# mux.net
KiCad netlist of a schematic drawn in Altium Designer
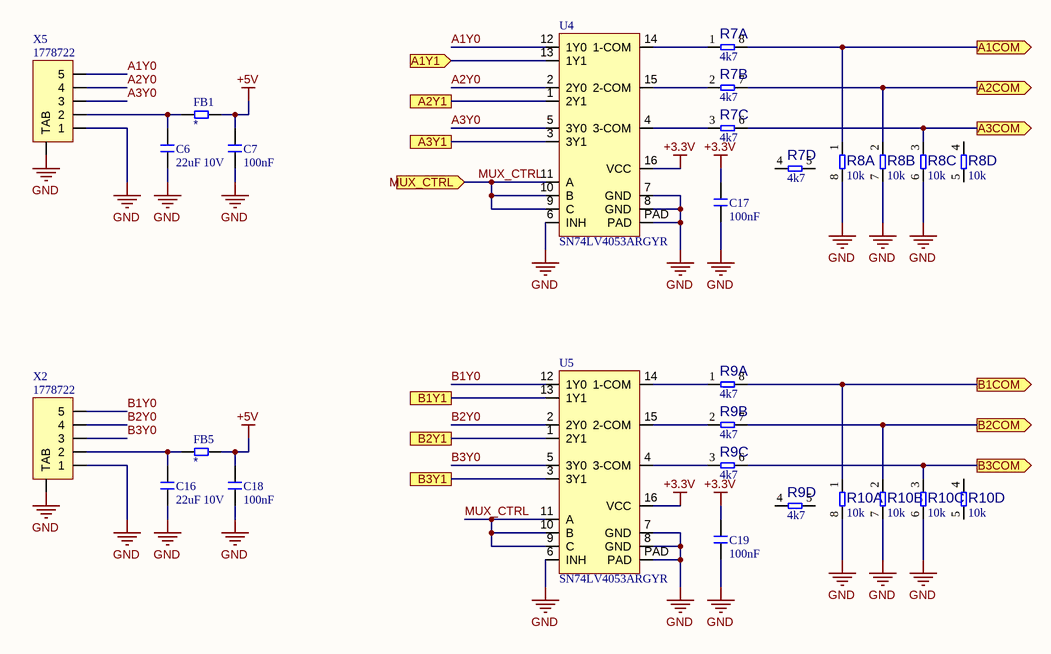
[diagram p0: mux.SchDoc]

(export (version "E")
  (design (tool "Eeschema 10.0.6"))
  (components
    (comp (ref "C6")
      (value "22uF 10V")
      (footprint "C1210_N")
      (description "Capacitor MLCC")
      (fields
        (field (name "MANUFACTURER") "Yageo")
        (field (name "MANUFACTURER PART NUMBER") "CC0603KRX7R9BB104")
      )
      (libsource (lib "wes") (part "Capacitor"))
    )
    (comp (ref "C7")
      (value "100nF")
      (footprint "C0603_N")
      (description "Capacitor MLCC")
      (fields
        (field (name "MANUFACTURER") "Yageo")
        (field (name "MANUFACTURER PART NUMBER") "CC0603KRX7R9BB104")
      )
      (libsource (lib "wes") (part "Capacitor"))
    )
    (comp (ref "C16")
      (value "22uF 10V")
      (footprint "C1210_N")
      (description "Capacitor MLCC")
      (fields
        (field (name "MANUFACTURER") "Yageo")
        (field (name "MANUFACTURER PART NUMBER") "CC0603KRX7R9BB104")
      )
      (libsource (lib "wes") (part "Capacitor"))
    )
    (comp (ref "C17")
      (value "100nF")
      (footprint "C0603_N")
      (description "Capacitor MLCC")
      (fields
        (field (name "MANUFACTURER") "Yageo")
        (field (name "MANUFACTURER PART NUMBER") "CC0603KRX7R9BB104")
      )
      (libsource (lib "wes") (part "Capacitor"))
    )
    (comp (ref "C18")
      (value "100nF")
      (footprint "C0603_N")
      (description "Capacitor MLCC")
      (fields
        (field (name "MANUFACTURER") "Yageo")
        (field (name "MANUFACTURER PART NUMBER") "CC0603KRX7R9BB104")
      )
      (libsource (lib "wes") (part "Capacitor"))
    )
    (comp (ref "C19")
      (value "100nF")
      (footprint "C0603_N")
      (description "Capacitor MLCC")
      (fields
        (field (name "MANUFACTURER") "Yageo")
        (field (name "MANUFACTURER PART NUMBER") "CC0603KRX7R9BB104")
      )
      (libsource (lib "wes") (part "Capacitor"))
    )
    (comp (ref "FB1")
      (value "Ferrite")
      (footprint "R0603")
      (fields (field (name "ALTIUM_VALUE") "*") (field (name "PUBLISHER") "Altium Limited"))
      (libsource (lib "wes") (part "Resistor"))
    )
    (comp (ref "FB5")
      (value "Ferrite")
      (footprint "R0603")
      (fields (field (name "ALTIUM_VALUE") "*") (field (name "PUBLISHER") "Altium Limited"))
      (libsource (lib "wes") (part "Resistor"))
    )
    (comp (ref "R7") (value "4k7") (footprint "YC164") (libsource (lib "wes") (part "Resistor Array - 4P")))
    (comp (ref "R8") (value "10k") (footprint "YC164") (libsource (lib "wes") (part "Resistor Array - 4P")))
    (comp (ref "R9") (value "4k7") (footprint "YC164") (libsource (lib "wes") (part "Resistor Array - 4P")))
    (comp (ref "R10") (value "10k") (footprint "YC164") (libsource (lib "wes") (part "Resistor Array - 4P")))
    (comp (ref "U4")
      (value "SN74LV4053ARGYR")
      (footprint "QFN16")
      (libsource (lib "wes") (part "SN74LV4053ARGYR"))
    )
    (comp (ref "U5")
      (value "SN74LV4053ARGYR")
      (footprint "QFN16")
      (libsource (lib "wes") (part "SN74LV4053ARGYR"))
    )
    (comp (ref "X2")
      (value "1778722")
      (footprint "PTSM-5W-V-SMD")
      (libsource (lib "wes") (part "Connector 5W - TAB"))
    )
    (comp (ref "X5")
      (value "1778722")
      (footprint "PTSM-5W-V-SMD")
      (libsource (lib "wes") (part "Connector 5W - TAB"))
    )
  )
  (nets
    (net (code "1") (name "+3.3V") (class "Default")
      (node (ref "C17") (pin "1") (pintype "passive"))
      (node (ref "C19") (pin "1") (pintype "passive"))
      (node (ref "U4") (pin "16") (pinfunction "VCC_16") (pintype "passive"))
      (node (ref "U5") (pin "16") (pinfunction "VCC_16") (pintype "passive"))
    )
    (net (code "2") (name "+5V") (class "Default")
      (node (ref "C18") (pin "1") (pintype "passive"))
      (node (ref "C7") (pin "1") (pintype "passive"))
      (node (ref "FB1") (pin "2") (pinfunction "2_2") (pintype "passive"))
      (node (ref "FB5") (pin "2") (pinfunction "2_2") (pintype "passive"))
    )
    (net (code "3") (name "/A1COM") (class "Default")
      (node (ref "R7") (pin "8") (pinfunction "8_8") (pintype "passive"))
      (node (ref "R8") (pin "1") (pinfunction "1_1") (pintype "passive"))
    )
    (net (code "4") (name "/A1Y0") (class "Default")
      (node (ref "U4") (pin "12") (pinfunction "1Y0_12") (pintype "passive"))
      (node (ref "X5") (pin "5") (pinfunction "5_5") (pintype "power_in"))
    )
    (net (code "5") (name "/A1Y1") (class "Default")
      (node (ref "U4") (pin "13") (pinfunction "1Y1_13") (pintype "passive"))
    )
    (net (code "6") (name "/A2COM") (class "Default")
      (node (ref "R7") (pin "7") (pinfunction "7_7") (pintype "passive"))
      (node (ref "R8") (pin "2") (pinfunction "2_2") (pintype "passive"))
    )
    (net (code "7") (name "/A2Y0") (class "Default")
      (node (ref "U4") (pin "2") (pinfunction "2Y0_2") (pintype "passive"))
      (node (ref "X5") (pin "4") (pinfunction "4_4") (pintype "power_in"))
    )
    (net (code "8") (name "/A2Y1") (class "Default")
      (node (ref "U4") (pin "1") (pinfunction "2Y1_1") (pintype "passive"))
    )
    (net (code "9") (name "/A3COM") (class "Default")
      (node (ref "R7") (pin "6") (pinfunction "6_6") (pintype "passive"))
      (node (ref "R8") (pin "3") (pinfunction "3_3") (pintype "passive"))
    )
    (net (code "10") (name "/A3Y0") (class "Default")
      (node (ref "U4") (pin "5") (pinfunction "3Y0_5") (pintype "passive"))
      (node (ref "X5") (pin "3") (pinfunction "3_3") (pintype "power_in"))
    )
    (net (code "11") (name "/A3Y1") (class "Default")
      (node (ref "U4") (pin "3") (pinfunction "3Y1_3") (pintype "passive"))
    )
    (net (code "12") (name "/B1COM") (class "Default")
      (node (ref "R10") (pin "1") (pinfunction "1_1") (pintype "passive"))
      (node (ref "R9") (pin "8") (pinfunction "8_8") (pintype "passive"))
    )
    (net (code "13") (name "/B1Y0") (class "Default")
      (node (ref "U5") (pin "12") (pinfunction "1Y0_12") (pintype "passive"))
      (node (ref "X2") (pin "5") (pinfunction "5_5") (pintype "power_in"))
    )
    (net (code "14") (name "/B1Y1") (class "Default")
      (node (ref "U5") (pin "13") (pinfunction "1Y1_13") (pintype "passive"))
    )
    (net (code "15") (name "/B2COM") (class "Default")
      (node (ref "R10") (pin "2") (pinfunction "2_2") (pintype "passive"))
      (node (ref "R9") (pin "7") (pinfunction "7_7") (pintype "passive"))
    )
    (net (code "16") (name "/B2Y0") (class "Default")
      (node (ref "U5") (pin "2") (pinfunction "2Y0_2") (pintype "passive"))
      (node (ref "X2") (pin "4") (pinfunction "4_4") (pintype "power_in"))
    )
    (net (code "17") (name "/B2Y1") (class "Default")
      (node (ref "U5") (pin "1") (pinfunction "2Y1_1") (pintype "passive"))
    )
    (net (code "18") (name "/B3COM") (class "Default")
      (node (ref "R10") (pin "3") (pinfunction "3_3") (pintype "passive"))
      (node (ref "R9") (pin "6") (pinfunction "6_6") (pintype "passive"))
    )
    (net (code "19") (name "/B3Y0") (class "Default")
      (node (ref "U5") (pin "5") (pinfunction "3Y0_5") (pintype "passive"))
      (node (ref "X2") (pin "3") (pinfunction "3_3") (pintype "power_in"))
    )
    (net (code "20") (name "/B3Y1") (class "Default")
      (node (ref "U5") (pin "3") (pinfunction "3Y1_3") (pintype "passive"))
    )
    (net (code "21") (name "/MUX_CTRL") (class "Default")
      (node (ref "U4") (pin "10") (pinfunction "B_10") (pintype "passive"))
      (node (ref "U4") (pin "11") (pinfunction "A_11") (pintype "passive"))
      (node (ref "U4") (pin "9") (pinfunction "C_9") (pintype "passive"))
      (node (ref "U5") (pin "10") (pinfunction "B_10") (pintype "passive"))
      (node (ref "U5") (pin "11") (pinfunction "A_11") (pintype "passive"))
      (node (ref "U5") (pin "9") (pinfunction "C_9") (pintype "passive"))
    )
    (net (code "22") (name "GND") (class "Default")
      (node (ref "C16") (pin "2") (pintype "passive"))
      (node (ref "C17") (pin "2") (pintype "passive"))
      (node (ref "C18") (pin "2") (pintype "passive"))
      (node (ref "C19") (pin "2") (pintype "passive"))
      (node (ref "C6") (pin "2") (pintype "passive"))
      (node (ref "C7") (pin "2") (pintype "passive"))
      (node (ref "R10") (pin "6") (pinfunction "6_6") (pintype "passive"))
      (node (ref "R10") (pin "7") (pinfunction "7_7") (pintype "passive"))
      (node (ref "R10") (pin "8") (pinfunction "8_8") (pintype "passive"))
      (node (ref "R8") (pin "6") (pinfunction "6_6") (pintype "passive"))
      (node (ref "R8") (pin "7") (pinfunction "7_7") (pintype "passive"))
      (node (ref "R8") (pin "8") (pinfunction "8_8") (pintype "passive"))
      (node (ref "U4") (pin "6") (pinfunction "INH_6") (pintype "passive"))
      (node (ref "U4") (pin "7") (pinfunction "GND_7") (pintype "passive"))
      (node (ref "U4") (pin "8") (pinfunction "GND_8") (pintype "passive"))
      (node (ref "U4") (pin "PAD") (pinfunction "PAD_PAD") (pintype "passive"))
      (node (ref "U5") (pin "6") (pinfunction "INH_6") (pintype "passive"))
      (node (ref "U5") (pin "7") (pinfunction "GND_7") (pintype "passive"))
      (node (ref "U5") (pin "8") (pinfunction "GND_8") (pintype "passive"))
      (node (ref "U5") (pin "PAD") (pinfunction "PAD_PAD") (pintype "passive"))
      (node (ref "X2") (pin "1") (pinfunction "1_1") (pintype "power_in"))
      (node (ref "X2") (pin "TAB") (pinfunction "TAB_TAB") (pintype "power_in"))
      (node (ref "X5") (pin "1") (pinfunction "1_1") (pintype "power_in"))
      (node (ref "X5") (pin "TAB") (pinfunction "TAB_TAB") (pintype "power_in"))
    )
    (net (code "23") (name "Net-(C6-Pad1)") (class "Default")
      (node (ref "C6") (pin "1") (pintype "passive"))
      (node (ref "FB1") (pin "1") (pinfunction "1_1") (pintype "passive"))
      (node (ref "X5") (pin "2") (pinfunction "2_2") (pintype "power_in"))
    )
    (net (code "24") (name "Net-(C16-Pad1)") (class "Default")
      (node (ref "C16") (pin "1") (pintype "passive"))
      (node (ref "FB5") (pin "1") (pinfunction "1_1") (pintype "passive"))
      (node (ref "X2") (pin "2") (pinfunction "2_2") (pintype "power_in"))
    )
    (net (code "25") (name "Net-(U4-1-COM)") (class "Default")
      (node (ref "R7") (pin "1") (pinfunction "1_1") (pintype "passive"))
      (node (ref "U4") (pin "14") (pinfunction "1-COM_14") (pintype "passive"))
    )
    (net (code "26") (name "Net-(U4-2-COM)") (class "Default")
      (node (ref "R7") (pin "2") (pinfunction "2_2") (pintype "passive"))
      (node (ref "U4") (pin "15") (pinfunction "2-COM_15") (pintype "passive"))
    )
    (net (code "27") (name "Net-(U4-3-COM)") (class "Default")
      (node (ref "R7") (pin "3") (pinfunction "3_3") (pintype "passive"))
      (node (ref "U4") (pin "4") (pinfunction "3-COM_4") (pintype "passive"))
    )
    (net (code "28") (name "Net-(U5-1-COM)") (class "Default")
      (node (ref "R9") (pin "1") (pinfunction "1_1") (pintype "passive"))
      (node (ref "U5") (pin "14") (pinfunction "1-COM_14") (pintype "passive"))
    )
    (net (code "29") (name "Net-(U5-2-COM)") (class "Default")
      (node (ref "R9") (pin "2") (pinfunction "2_2") (pintype "passive"))
      (node (ref "U5") (pin "15") (pinfunction "2-COM_15") (pintype "passive"))
    )
    (net (code "30") (name "Net-(U5-3-COM)") (class "Default")
      (node (ref "R9") (pin "3") (pinfunction "3_3") (pintype "passive"))
      (node (ref "U5") (pin "4") (pinfunction "3-COM_4") (pintype "passive"))
    )
    (net (code "31") (name "unconnected-(R7-Pad4)") (class "Default")
      (node (ref "R7") (pin "4") (pinfunction "4_4") (pintype "passive"))
    )
    (net (code "32") (name "unconnected-(R7-Pad5)") (class "Default")
      (node (ref "R7") (pin "5") (pinfunction "5_5") (pintype "passive"))
    )
    (net (code "33") (name "unconnected-(R8-Pad4)") (class "Default")
      (node (ref "R8") (pin "4") (pinfunction "4_4") (pintype "passive"))
    )
    (net (code "34") (name "unconnected-(R8-Pad5)") (class "Default")
      (node (ref "R8") (pin "5") (pinfunction "5_5") (pintype "passive"))
    )
    (net (code "35") (name "unconnected-(R9-Pad4)") (class "Default")
      (node (ref "R9") (pin "4") (pinfunction "4_4") (pintype "passive"))
    )
    (net (code "36") (name "unconnected-(R9-Pad5)") (class "Default")
      (node (ref "R9") (pin "5") (pinfunction "5_5") (pintype "passive"))
    )
    (net (code "37") (name "unconnected-(R10-Pad4)") (class "Default")
      (node (ref "R10") (pin "4") (pinfunction "4_4") (pintype "passive"))
    )
    (net (code "38") (name "unconnected-(R10-Pad5)") (class "Default")
      (node (ref "R10") (pin "5") (pinfunction "5_5") (pintype "passive"))
    )
  )
)
